# Lipmouse_PCB.net
KiCad netlist of a schematic drawn in EAGLE
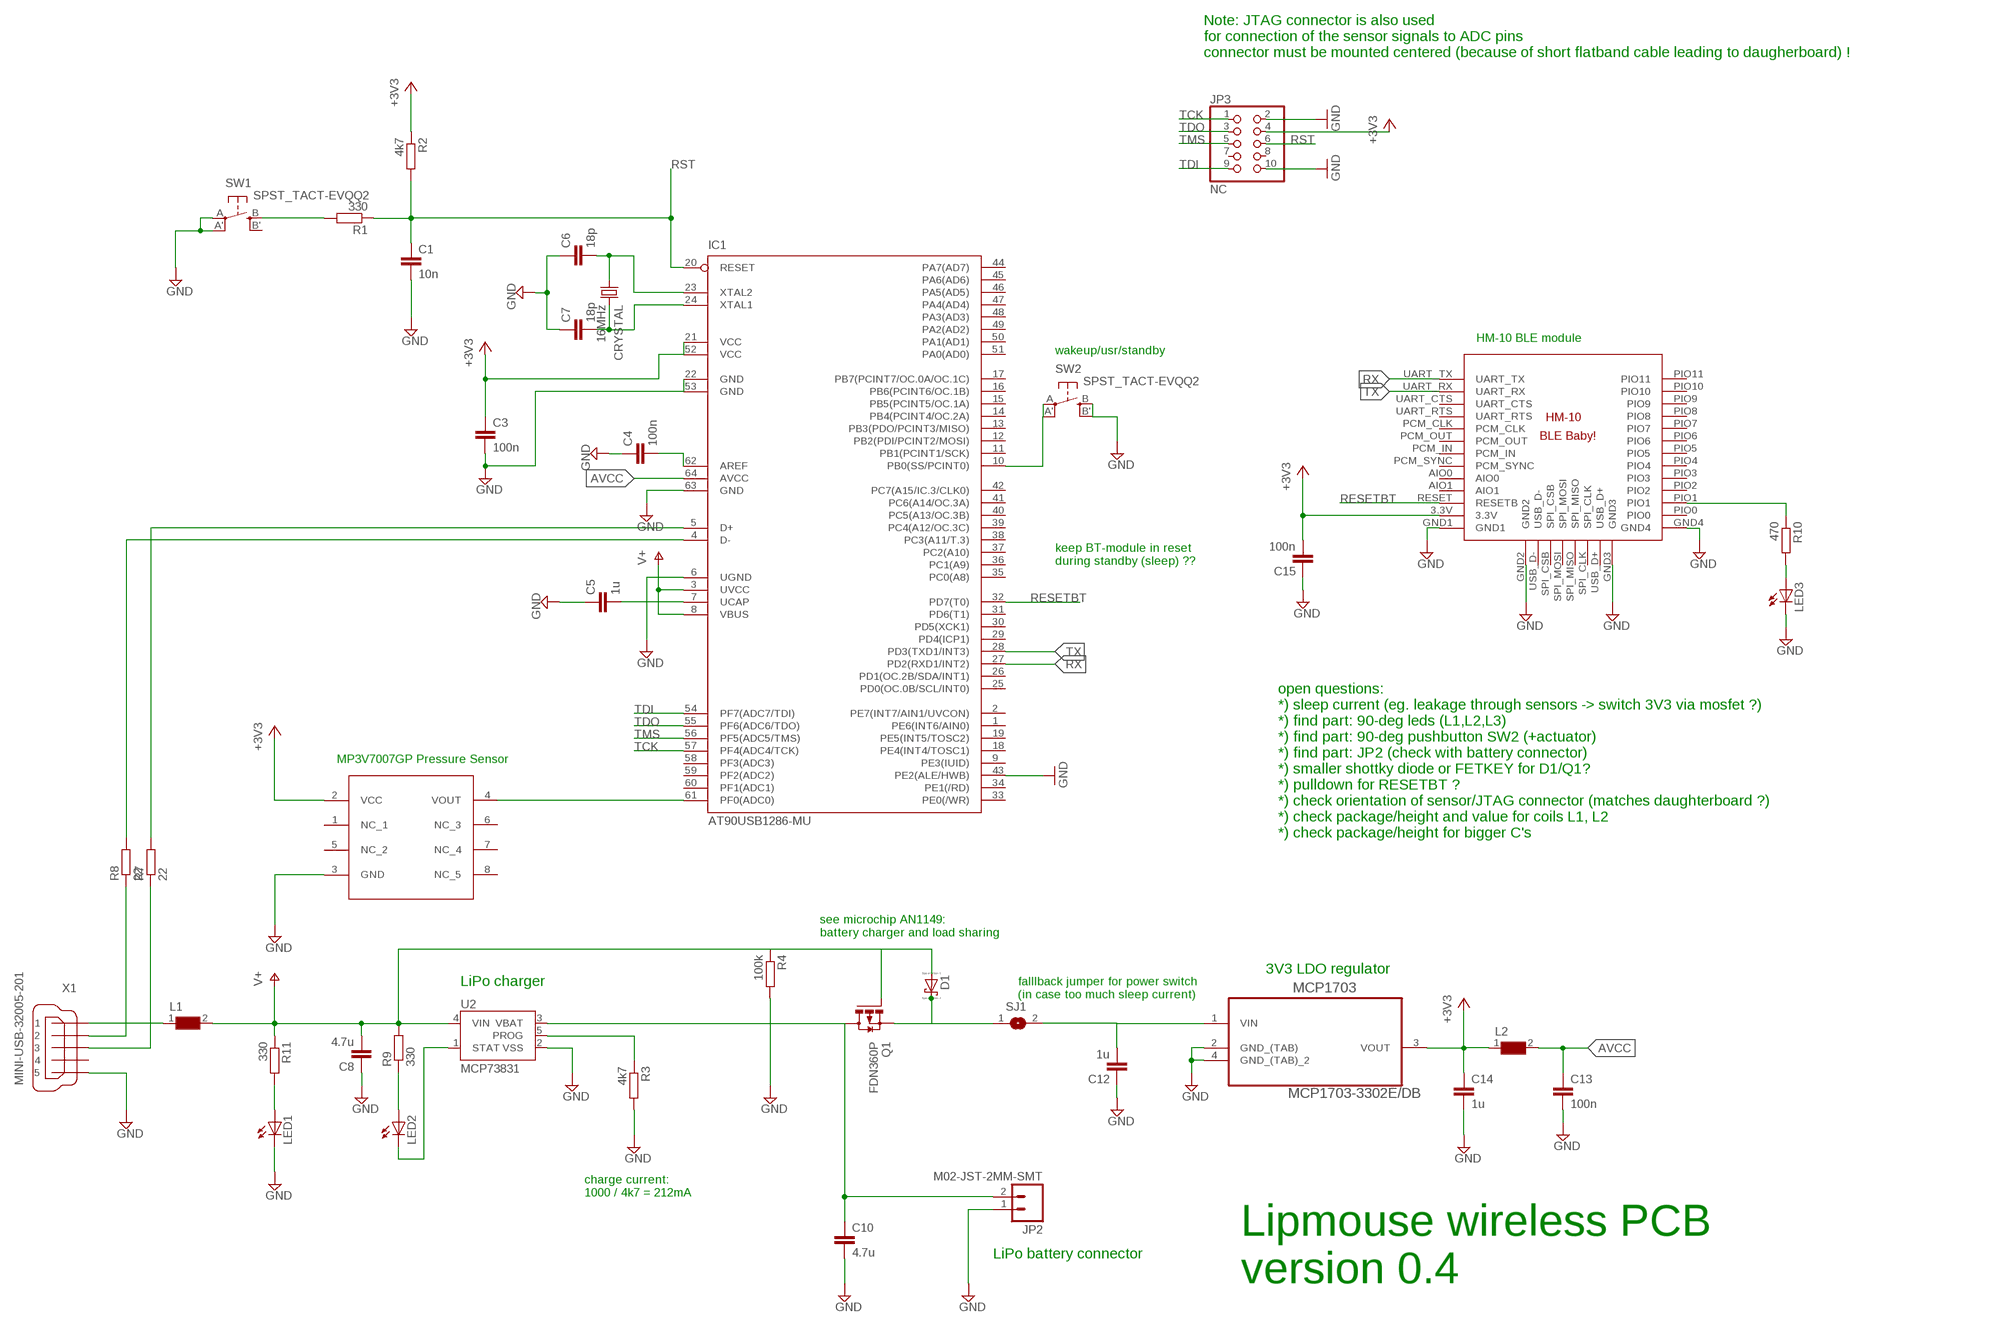
[diagram p0: schematic, sheet 1]

(export (version "E")
  (design (tool "Eeschema 10.0.6"))
  (components
    (comp (ref "C1")
      (value "10n")
      (footprint "eagle-import:C0603")
      (libsource (lib "eagle-import") (part "C-EUC0603"))
    )
    (comp (ref "C3")
      (value "100n")
      (footprint "eagle-import:C0603")
      (libsource (lib "eagle-import") (part "C-EUC0603"))
    )
    (comp (ref "C4")
      (value "100n")
      (footprint "eagle-import:C0603")
      (libsource (lib "eagle-import") (part "C-EUC0603"))
    )
    (comp (ref "C5")
      (value "1u")
      (footprint "eagle-import:C0603")
      (libsource (lib "eagle-import") (part "C-EUC0603"))
    )
    (comp (ref "C6")
      (value "18p")
      (footprint "eagle-import:C0603")
      (libsource (lib "eagle-import") (part "C-EUC0603"))
    )
    (comp (ref "C7")
      (value "18p")
      (footprint "eagle-import:C0603")
      (libsource (lib "eagle-import") (part "C-EUC0603"))
    )
    (comp (ref "C8")
      (value "4.7u")
      (footprint "eagle-import:C0805")
      (libsource (lib "eagle-import") (part "C-EUC0805"))
    )
    (comp (ref "C10")
      (value "4.7u")
      (footprint "eagle-import:C0805")
      (libsource (lib "eagle-import") (part "C-EUC0805"))
    )
    (comp (ref "C12")
      (value "1u")
      (footprint "eagle-import:C0603")
      (libsource (lib "eagle-import") (part "C-EUC0603"))
    )
    (comp (ref "C13")
      (value "100n")
      (footprint "eagle-import:C0603")
      (libsource (lib "eagle-import") (part "C-EUC0603"))
    )
    (comp (ref "C14")
      (value "1u")
      (footprint "eagle-import:C0603")
      (libsource (lib "eagle-import") (part "C-EUC0603"))
    )
    (comp (ref "C15")
      (value "100n")
      (footprint "eagle-import:C0603")
      (libsource (lib "eagle-import") (part "C-EUC0603"))
    )
    (comp (ref "CRYSTAL")
      (value "16MHz")
      (footprint "eagle-import:CRYSTAL-TXC-7A")
      (libsource (lib "eagle-import") (part "CRYSTALTXC-7A"))
    )
    (comp (ref "D1")
      (value "SCHOTTKY-DIODE")
      (footprint "eagle-import:DIODE_SMB")
      (libsource (lib "eagle-import") (part "SCHOTTKY-DIODE"))
    )
    (comp (ref "IC1")
      (value "AT90USB1286-MU")
      (footprint "eagle-import:TQFP64")
      (libsource (lib "eagle-import") (part "AT90USB1287-AU"))
    )
    (comp (ref "JP2")
      (value "M02-JST-2MM-SMT")
      (footprint "eagle-import:JST-2-SMD")
      (libsource (lib "eagle-import") (part "M02-JST-2MM-SMT"))
    )
    (comp (ref "JP3")
      (value "NC")
      (footprint "eagle-import:2X05")
      (libsource (lib "eagle-import") (part "PINHD-2X5"))
    )
    (comp (ref "L1")
      (value "WE-CBF-74279201_0805")
      (footprint "eagle-import:0805")
      (fields (field (name "MPN") "74279201"))
      (libsource (lib "eagle-import") (part "WE-CBF_0805-74279201"))
    )
    (comp (ref "L2")
      (value "WE-CBF-74279201_0805")
      (footprint "eagle-import:0805")
      (fields (field (name "MPN") "74279201"))
      (libsource (lib "eagle-import") (part "WE-CBF_0805-74279201"))
    )
    (comp (ref "LED1")
      (value "LEDSMT1206")
      (footprint "eagle-import:1206")
      (libsource (lib "eagle-import") (part "LEDSMT1206"))
    )
    (comp (ref "LED2")
      (value "LEDSMT1206")
      (footprint "eagle-import:1206")
      (libsource (lib "eagle-import") (part "LEDSMT1206"))
    )
    (comp (ref "LED3")
      (value "LEDSMT1206")
      (footprint "eagle-import:1206")
      (libsource (lib "eagle-import") (part "LEDSMT1206"))
    )
    (comp (ref "MCP1703")
      (value "MCP1703-3302E/DB")
      (footprint "eagle-import:SOT230P700X180-4N")
      (libsource (lib "eagle-import") (part "MCP1703-3302E/DB"))
    )
    (comp (ref "MP3V7007")
      (value "MP3V7007GP")
      (footprint "eagle-import:SMP_MP3V7007")
      (libsource (lib "eagle-import") (part "MP3V7007GP"))
    )
    (comp (ref "Q1")
      (value "FDN360P")
      (footprint "eagle-import:SUPER-SOT3")
      (libsource (lib "eagle-import") (part "FDN360P"))
    )
    (comp (ref "R1")
      (value "330")
      (footprint "eagle-import:R0603")
      (libsource (lib "eagle-import") (part "R-EU_R0603"))
    )
    (comp (ref "R2")
      (value "4k7")
      (footprint "eagle-import:R0603")
      (libsource (lib "eagle-import") (part "R-EU_R0603"))
    )
    (comp (ref "R3")
      (value "4k7")
      (footprint "eagle-import:R0603")
      (libsource (lib "eagle-import") (part "R-EU_R0603"))
    )
    (comp (ref "R4")
      (value "100k")
      (footprint "eagle-import:R0603")
      (libsource (lib "eagle-import") (part "R-EU_R0603"))
    )
    (comp (ref "R7")
      (value "22")
      (footprint "eagle-import:R0603")
      (libsource (lib "eagle-import") (part "R-EU_R0603"))
    )
    (comp (ref "R8")
      (value "22")
      (footprint "eagle-import:R0603")
      (libsource (lib "eagle-import") (part "R-EU_R0603"))
    )
    (comp (ref "R9")
      (value "330")
      (footprint "eagle-import:R0603")
      (libsource (lib "eagle-import") (part "R-EU_R0603"))
    )
    (comp (ref "R10")
      (value "470")
      (footprint "eagle-import:R0603")
      (libsource (lib "eagle-import") (part "R-EU_R0603"))
    )
    (comp (ref "R11")
      (value "330")
      (footprint "eagle-import:R0603")
      (libsource (lib "eagle-import") (part "R-EU_R0603"))
    )
    (comp (ref "SJ1") (value "SJ") (footprint "eagle-import:SJ") (libsource (lib "eagle-import") (part "SJ")))
    (comp (ref "SW1")
      (value "SPST_TACT-EVQQ2")
      (footprint "eagle-import:EVQ-Q2")
      (libsource (lib "eagle-import") (part "SPST_TACT-EVQQ2"))
    )
    (comp (ref "SW2")
      (value "SPST_TACT-EVQQ2")
      (footprint "eagle-import:EVQ-Q2")
      (libsource (lib "eagle-import") (part "SPST_TACT-EVQQ2"))
    )
    (comp (ref "U$1")
      (value "BLE-HM-10")
      (footprint "eagle-import:BLE-HM-10")
      (libsource (lib "eagle-import") (part "BLE-HM-10"))
    )
    (comp (ref "U2")
      (value "MCP73831")
      (footprint "eagle-import:SOT23-5")
      (libsource (lib "eagle-import") (part "MCP73831"))
    )
    (comp (ref "X1")
      (value "MINI-USB-32005-201")
      (footprint "eagle-import:32005-201")
      (libsource (lib "eagle-import") (part "MINI-USB-32005-201"))
    )
  )
  (nets
    (net (code "1") (name "+3V3") (class "Default")
      (node (ref "C14") (pin "1") (pinfunction "1_1") (pintype "passive"))
      (node (ref "C15") (pin "2") (pinfunction "2_2") (pintype "passive"))
      (node (ref "C3") (pin "1") (pinfunction "1_1") (pintype "passive"))
      (node (ref "IC1") (pin "21") (pinfunction "VCC_21") (pintype "power_in"))
      (node (ref "IC1") (pin "52") (pinfunction "VCC_52") (pintype "power_in"))
      (node (ref "JP3") (pin "4") (pinfunction "4_4") (pintype "passive"))
      (node (ref "L2") (pin "1") (pinfunction "1_1") (pintype "passive"))
      (node (ref "MCP1703") (pin "3") (pinfunction "VOUT_3") (pintype "output"))
      (node (ref "MP3V7007") (pin "2") (pinfunction "VCC_2") (pintype "bidirectional"))
      (node (ref "R2") (pin "1") (pinfunction "1_1") (pintype "passive"))
      (node (ref "U$1") (pin "3.3V") (pinfunction "3.3V_3.3V") (pintype "bidirectional"))
    )
    (net (code "2") (name "/RESETBT") (class "Default")
      (node (ref "IC1") (pin "32") (pinfunction "PD7(T0)_32") (pintype "bidirectional"))
      (node (ref "U$1") (pin "RESET") (pinfunction "RESETB_RESET") (pintype "bidirectional"))
    )
    (net (code "3") (name "/RST") (class "Default")
      (node (ref "C1") (pin "1") (pinfunction "1_1") (pintype "passive"))
      (node (ref "IC1") (pin "20") (pinfunction "RESET_20") (pintype "input"))
      (node (ref "JP3") (pin "6") (pinfunction "6_6") (pintype "passive"))
      (node (ref "R1") (pin "1") (pinfunction "1_1") (pintype "passive"))
      (node (ref "R2") (pin "2") (pinfunction "2_2") (pintype "passive"))
    )
    (net (code "4") (name "/TCK") (class "Default")
      (node (ref "IC1") (pin "57") (pinfunction "PF4(ADC4/TCK)_57") (pintype "bidirectional"))
      (node (ref "JP3") (pin "1") (pinfunction "1_1") (pintype "passive"))
    )
    (net (code "5") (name "/TDI") (class "Default")
      (node (ref "IC1") (pin "54") (pinfunction "PF7(ADC7/TDI)_54") (pintype "bidirectional"))
      (node (ref "JP3") (pin "9") (pinfunction "9_9") (pintype "passive"))
    )
    (net (code "6") (name "/TDO") (class "Default")
      (node (ref "IC1") (pin "55") (pinfunction "PF6(ADC6/TDO)_55") (pintype "bidirectional"))
      (node (ref "JP3") (pin "3") (pinfunction "3_3") (pintype "passive"))
    )
    (net (code "7") (name "/TMS") (class "Default")
      (node (ref "IC1") (pin "56") (pinfunction "PF5(ADC5/TMS)_56") (pintype "bidirectional"))
      (node (ref "JP3") (pin "5") (pinfunction "5_5") (pintype "passive"))
    )
    (net (code "8") (name "AVCC") (class "Default")
      (node (ref "C13") (pin "1") (pinfunction "1_1") (pintype "passive"))
      (node (ref "IC1") (pin "64") (pinfunction "AVCC_64") (pintype "bidirectional"))
      (node (ref "L2") (pin "2") (pinfunction "2_2") (pintype "passive"))
    )
    (net (code "9") (name "GND") (class "Default")
      (node (ref "C1") (pin "2") (pinfunction "2_2") (pintype "passive"))
      (node (ref "C10") (pin "2") (pinfunction "2_2") (pintype "passive"))
      (node (ref "C12") (pin "1") (pinfunction "1_1") (pintype "passive"))
      (node (ref "C13") (pin "2") (pinfunction "2_2") (pintype "passive"))
      (node (ref "C14") (pin "2") (pinfunction "2_2") (pintype "passive"))
      (node (ref "C15") (pin "1") (pinfunction "1_1") (pintype "passive"))
      (node (ref "C3") (pin "2") (pinfunction "2_2") (pintype "passive"))
      (node (ref "C4") (pin "1") (pinfunction "1_1") (pintype "passive"))
      (node (ref "C5") (pin "1") (pinfunction "1_1") (pintype "passive"))
      (node (ref "C6") (pin "1") (pinfunction "1_1") (pintype "passive"))
      (node (ref "C7") (pin "1") (pinfunction "1_1") (pintype "passive"))
      (node (ref "C8") (pin "1") (pinfunction "1_1") (pintype "passive"))
      (node (ref "IC1") (pin "22") (pinfunction "GND_22") (pintype "power_in"))
      (node (ref "IC1") (pin "43") (pinfunction "PE2(ALE/HWB)_43") (pintype "bidirectional"))
      (node (ref "IC1") (pin "53") (pinfunction "GND_53") (pintype "power_in"))
      (node (ref "IC1") (pin "6") (pinfunction "UGND_6") (pintype "power_in"))
      (node (ref "IC1") (pin "63") (pinfunction "GND_63") (pintype "power_in"))
      (node (ref "JP2") (pin "1") (pinfunction "2_1") (pintype "passive"))
      (node (ref "JP3") (pin "10") (pinfunction "10_10") (pintype "passive"))
      (node (ref "JP3") (pin "2") (pinfunction "2_2") (pintype "passive"))
      (node (ref "LED1") (pin "C") (pinfunction "C_C") (pintype "passive"))
      (node (ref "LED3") (pin "C") (pinfunction "C_C") (pintype "passive"))
      (node (ref "MCP1703") (pin "2") (pinfunction "GND_(TAB)_2") (pintype "passive"))
      (node (ref "MCP1703") (pin "4") (pinfunction "GND_(TAB)_2_4") (pintype "passive"))
      (node (ref "MP3V7007") (pin "3") (pinfunction "GND_3") (pintype "bidirectional"))
      (node (ref "R3") (pin "2") (pinfunction "2_2") (pintype "passive"))
      (node (ref "R4") (pin "2") (pinfunction "2_2") (pintype "passive"))
      (node (ref "SW1") (pin "A") (pinfunction "P_A") (pintype "passive"))
      (node (ref "SW1") (pin "A'") (pinfunction "P1_A'") (pintype "passive"))
      (node (ref "SW2") (pin "B") (pinfunction "S_B") (pintype "passive"))
      (node (ref "SW2") (pin "B'") (pinfunction "S1_B'") (pintype "passive"))
      (node (ref "U$1") (pin "GND1") (pinfunction "GND1_GND1") (pintype "bidirectional"))
      (node (ref "U$1") (pin "GND2") (pinfunction "GND2_GND2") (pintype "bidirectional"))
      (node (ref "U$1") (pin "GND3") (pinfunction "GND3_GND3") (pintype "bidirectional"))
      (node (ref "U$1") (pin "GND4") (pinfunction "GND4_GND4") (pintype "bidirectional"))
      (node (ref "U2") (pin "2") (pinfunction "VSS_2") (pintype "power_in"))
      (node (ref "X1") (pin "5") (pinfunction "5_5") (pintype "passive"))
    )
    (net (code "10") (name "Net-(CRYSTAL-1)") (class "Default")
      (node (ref "C6") (pin "2") (pinfunction "2_2") (pintype "passive"))
      (node (ref "CRYSTAL") (pin "P$1") (pinfunction "1_P$1") (pintype "passive"))
      (node (ref "IC1") (pin "23") (pinfunction "XTAL2_23") (pintype "bidirectional"))
    )
    (net (code "11") (name "Net-(CRYSTAL-2)") (class "Default")
      (node (ref "C7") (pin "2") (pinfunction "2_2") (pintype "passive"))
      (node (ref "CRYSTAL") (pin "P$2") (pinfunction "2_P$2") (pintype "passive"))
      (node (ref "IC1") (pin "24") (pinfunction "XTAL1_24") (pintype "bidirectional"))
    )
    (net (code "12") (name "Net-(D1-A)") (class "Default")
      (node (ref "D1") (pin "C") (pinfunction "A_C") (pintype "passive"))
      (node (ref "Q1") (pin "2") (pinfunction "S_2") (pintype "passive"))
      (node (ref "SJ1") (pin "1") (pinfunction "1_1") (pintype "passive"))
    )
    (net (code "13") (name "Net-(IC1-AREF)") (class "Default")
      (node (ref "C4") (pin "2") (pinfunction "2_2") (pintype "passive"))
      (node (ref "IC1") (pin "62") (pinfunction "AREF_62") (pintype "bidirectional"))
    )
    (net (code "14") (name "Net-(IC1-D+)") (class "Default")
      (node (ref "IC1") (pin "5") (pinfunction "D+_5") (pintype "bidirectional"))
      (node (ref "R7") (pin "2") (pinfunction "2_2") (pintype "passive"))
    )
    (net (code "15") (name "Net-(IC1-D-)") (class "Default")
      (node (ref "IC1") (pin "4") (pinfunction "D-_4") (pintype "bidirectional"))
      (node (ref "R8") (pin "2") (pinfunction "2_2") (pintype "passive"))
    )
    (net (code "16") (name "Net-(IC1-PB0(SS{slash}PCINT0))") (class "Default")
      (node (ref "IC1") (pin "10") (pinfunction "PB0(SS/PCINT0)_10") (pintype "bidirectional"))
      (node (ref "SW2") (pin "A") (pinfunction "P_A") (pintype "passive"))
      (node (ref "SW2") (pin "A'") (pinfunction "P1_A'") (pintype "passive"))
    )
    (net (code "17") (name "Net-(IC1-PF0(ADC0))") (class "Default")
      (node (ref "IC1") (pin "61") (pinfunction "PF0(ADC0)_61") (pintype "bidirectional"))
      (node (ref "MP3V7007") (pin "4") (pinfunction "VOUT_4") (pintype "bidirectional"))
    )
    (net (code "18") (name "Net-(IC1-UCAP)") (class "Default")
      (node (ref "C5") (pin "2") (pinfunction "2_2") (pintype "passive"))
      (node (ref "IC1") (pin "7") (pinfunction "UCAP_7") (pintype "power_in"))
    )
    (net (code "19") (name "Net-(JP2-1)") (class "Default")
      (node (ref "C10") (pin "1") (pinfunction "1_1") (pintype "passive"))
      (node (ref "JP2") (pin "2") (pinfunction "1_2") (pintype "passive"))
      (node (ref "Q1") (pin "3") (pinfunction "D_3") (pintype "passive"))
      (node (ref "U2") (pin "3") (pinfunction "VBAT_3") (pintype "power_in"))
    )
    (net (code "20") (name "Net-(L1-Pad1)") (class "Default")
      (node (ref "L1") (pin "1") (pinfunction "1_1") (pintype "passive"))
      (node (ref "X1") (pin "1") (pinfunction "1_1") (pintype "passive"))
    )
    (net (code "21") (name "Net-(LED1-PadA)") (class "Default")
      (node (ref "LED1") (pin "A") (pinfunction "A_A") (pintype "passive"))
      (node (ref "R11") (pin "2") (pinfunction "2_2") (pintype "passive"))
    )
    (net (code "22") (name "Net-(LED2-PadA)") (class "Default")
      (node (ref "LED2") (pin "A") (pinfunction "A_A") (pintype "passive"))
      (node (ref "R9") (pin "1") (pinfunction "1_1") (pintype "passive"))
    )
    (net (code "23") (name "Net-(LED3-PadA)") (class "Default")
      (node (ref "LED3") (pin "A") (pinfunction "A_A") (pintype "passive"))
      (node (ref "R10") (pin "2") (pinfunction "2_2") (pintype "passive"))
    )
    (net (code "24") (name "Net-(MCP1703-VIN)") (class "Default")
      (node (ref "C12") (pin "2") (pinfunction "2_2") (pintype "passive"))
      (node (ref "MCP1703") (pin "1") (pinfunction "VIN_1") (pintype "input"))
      (node (ref "SJ1") (pin "2") (pinfunction "2_2") (pintype "passive"))
    )
    (net (code "25") (name "Net-(R7-Pad1)") (class "Default")
      (node (ref "R7") (pin "1") (pinfunction "1_1") (pintype "passive"))
      (node (ref "X1") (pin "3") (pinfunction "3_3") (pintype "passive"))
    )
    (net (code "26") (name "Net-(R8-Pad1)") (class "Default")
      (node (ref "R8") (pin "1") (pinfunction "1_1") (pintype "passive"))
      (node (ref "X1") (pin "2") (pinfunction "2_2") (pintype "passive"))
    )
    (net (code "27") (name "Net-(R10-Pad1)") (class "Default")
      (node (ref "R10") (pin "1") (pinfunction "1_1") (pintype "passive"))
      (node (ref "U$1") (pin "PIO1") (pinfunction "PIO1_PIO1") (pintype "bidirectional"))
    )
    (net (code "28") (name "Net-(SW1-S)") (class "Default")
      (node (ref "R1") (pin "2") (pinfunction "2_2") (pintype "passive"))
      (node (ref "SW1") (pin "B") (pinfunction "S_B") (pintype "passive"))
    )
    (net (code "29") (name "Net-(U2-PROG)") (class "Default")
      (node (ref "R3") (pin "1") (pinfunction "1_1") (pintype "passive"))
      (node (ref "U2") (pin "5") (pinfunction "PROG_5") (pintype "input"))
    )
    (net (code "30") (name "Net-(U2-STAT)") (class "Default")
      (node (ref "LED2") (pin "C") (pinfunction "C_C") (pintype "passive"))
      (node (ref "U2") (pin "1") (pinfunction "STAT_1") (pintype "output"))
    )
    (net (code "31") (name "RX") (class "Default")
      (node (ref "IC1") (pin "27") (pinfunction "PD2(RXD1/INT2)_27") (pintype "bidirectional"))
      (node (ref "U$1") (pin "UART_TX") (pinfunction "UART_TX_UART_TX") (pintype "bidirectional"))
    )
    (net (code "32") (name "TX") (class "Default")
      (node (ref "IC1") (pin "28") (pinfunction "PD3(TXD1/INT3)_28") (pintype "bidirectional"))
      (node (ref "U$1") (pin "UART_RX") (pinfunction "UART_RX_UART_RX") (pintype "bidirectional"))
    )
    (net (code "33") (name "V+") (class "Default")
      (node (ref "C8") (pin "2") (pinfunction "2_2") (pintype "passive"))
      (node (ref "D1") (pin "A") (pinfunction "C_A") (pintype "passive"))
      (node (ref "IC1") (pin "3") (pinfunction "UVCC_3") (pintype "power_in"))
      (node (ref "IC1") (pin "8") (pinfunction "VBUS_8") (pintype "power_in"))
      (node (ref "L1") (pin "2") (pinfunction "2_2") (pintype "passive"))
      (node (ref "Q1") (pin "1") (pinfunction "G_1") (pintype "passive"))
      (node (ref "R11") (pin "1") (pinfunction "1_1") (pintype "passive"))
      (node (ref "R4") (pin "1") (pinfunction "1_1") (pintype "passive"))
      (node (ref "R9") (pin "2") (pinfunction "2_2") (pintype "passive"))
      (node (ref "U2") (pin "4") (pinfunction "VIN_4") (pintype "power_in"))
    )
    (net (code "34") (name "unconnected-(IC1-PA0(AD0)-Pad51)") (class "Default")
      (node (ref "IC1") (pin "51") (pinfunction "PA0(AD0)_51") (pintype "bidirectional"))
    )
    (net (code "35") (name "unconnected-(IC1-PA1(AD1)-Pad50)") (class "Default")
      (node (ref "IC1") (pin "50") (pinfunction "PA1(AD1)_50") (pintype "bidirectional"))
    )
    (net (code "36") (name "unconnected-(IC1-PA2(AD2)-Pad49)") (class "Default")
      (node (ref "IC1") (pin "49") (pinfunction "PA2(AD2)_49") (pintype "bidirectional"))
    )
    (net (code "37") (name "unconnected-(IC1-PA3(AD3)-Pad48)") (class "Default")
      (node (ref "IC1") (pin "48") (pinfunction "PA3(AD3)_48") (pintype "bidirectional"))
    )
    (net (code "38") (name "unconnected-(IC1-PA4(AD4)-Pad47)") (class "Default")
      (node (ref "IC1") (pin "47") (pinfunction "PA4(AD4)_47") (pintype "bidirectional"))
    )
    (net (code "39") (name "unconnected-(IC1-PA5(AD5)-Pad46)") (class "Default")
      (node (ref "IC1") (pin "46") (pinfunction "PA5(AD5)_46") (pintype "bidirectional"))
    )
    (net (code "40") (name "unconnected-(IC1-PA6(AD6)-Pad45)") (class "Default")
      (node (ref "IC1") (pin "45") (pinfunction "PA6(AD6)_45") (pintype "bidirectional"))
    )
    (net (code "41") (name "unconnected-(IC1-PA7(AD7)-Pad44)") (class "Default")
      (node (ref "IC1") (pin "44") (pinfunction "PA7(AD7)_44") (pintype "bidirectional"))
    )
    (net (code "42") (name "unconnected-(IC1-PB1(PCINT1{slash}SCK)-Pad11)") (class "Default")
      (node (ref "IC1") (pin "11") (pinfunction "PB1(PCINT1/SCK)_11") (pintype "bidirectional"))
    )
    (net (code "43") (name "unconnected-(IC1-PB2(PDI{slash}PCINT2{slash}MOSI)-Pad12)") (class "Default")
      (node (ref "IC1") (pin "12") (pinfunction "PB2(PDI/PCINT2/MOSI)_12") (pintype "bidirectional"))
    )
    (net (code "44") (name "unconnected-(IC1-PB3(PDO{slash}PCINT3{slash}MISO)-Pad13)") (class "Default")
      (node (ref "IC1") (pin "13") (pinfunction "PB3(PDO/PCINT3/MISO)_13") (pintype "bidirectional"))
    )
    (net (code "45") (name "unconnected-(IC1-PB4(PCINT4{slash}OC.2A)-Pad14)") (class "Default")
      (node (ref "IC1") (pin "14") (pinfunction "PB4(PCINT4/OC.2A)_14") (pintype "bidirectional"))
    )
    (net (code "46") (name "unconnected-(IC1-PB5(PCINT5{slash}OC.1A)-Pad15)") (class "Default")
      (node (ref "IC1") (pin "15") (pinfunction "PB5(PCINT5/OC.1A)_15") (pintype "bidirectional"))
    )
    (net (code "47") (name "unconnected-(IC1-PB6(PCINT6{slash}OC.1B)-Pad16)") (class "Default")
      (node (ref "IC1") (pin "16") (pinfunction "PB6(PCINT6/OC.1B)_16") (pintype "bidirectional"))
    )
    (net (code "48") (name "unconnected-(IC1-PB7(PCINT7{slash}OC.0A{slash}OC.1C)-Pad17)") (class "Default")
      (node (ref "IC1") (pin "17") (pinfunction "PB7(PCINT7/OC.0A/OC.1C)_17") (pintype "bidirectional"))
    )
    (net (code "49") (name "unconnected-(IC1-PC0(A8)-Pad35)") (class "Default")
      (node (ref "IC1") (pin "35") (pinfunction "PC0(A8)_35") (pintype "bidirectional"))
    )
    (net (code "50") (name "unconnected-(IC1-PC1(A9)-Pad36)") (class "Default")
      (node (ref "IC1") (pin "36") (pinfunction "PC1(A9)_36") (pintype "bidirectional"))
    )
    (net (code "51") (name "unconnected-(IC1-PC2(A10)-Pad37)") (class "Default")
      (node (ref "IC1") (pin "37") (pinfunction "PC2(A10)_37") (pintype "bidirectional"))
    )
    (net (code "52") (name "unconnected-(IC1-PC3(A11{slash}T.3)-Pad38)") (class "Default")
      (node (ref "IC1") (pin "38") (pinfunction "PC3(A11/T.3)_38") (pintype "bidirectional"))
    )
    (net (code "53") (name "unconnected-(IC1-PC4(A12{slash}OC.3C)-Pad39)") (class "Default")
      (node (ref "IC1") (pin "39") (pinfunction "PC4(A12/OC.3C)_39") (pintype "bidirectional"))
    )
    (net (code "54") (name "unconnected-(IC1-PC5(A13{slash}OC.3B)-Pad40)") (class "Default")
      (node (ref "IC1") (pin "40") (pinfunction "PC5(A13/OC.3B)_40") (pintype "bidirectional"))
    )
    (net (code "55") (name "unconnected-(IC1-PC6(A14{slash}OC.3A)-Pad41)") (class "Default")
      (node (ref "IC1") (pin "41") (pinfunction "PC6(A14/OC.3A)_41") (pintype "bidirectional"))
    )
    (net (code "56") (name "unconnected-(IC1-PC7(A15{slash}IC.3{slash}CLK0)-Pad42)") (class "Default")
      (node (ref "IC1") (pin "42") (pinfunction "PC7(A15/IC.3/CLK0)_42") (pintype "bidirectional"))
    )
    (net (code "57") (name "unconnected-(IC1-PD0(OC.0B{slash}SCL{slash}INT0)-Pad25)") (class "Default")
      (node (ref "IC1") (pin "25") (pinfunction "PD0(OC.0B/SCL/INT0)_25") (pintype "bidirectional"))
    )
    (net (code "58") (name "unconnected-(IC1-PD1(OC.2B{slash}SDA{slash}INT1)-Pad26)") (class "Default")
      (node (ref "IC1") (pin "26") (pinfunction "PD1(OC.2B/SDA/INT1)_26") (pintype "bidirectional"))
    )
    (net (code "59") (name "unconnected-(IC1-PD4(ICP1)-Pad29)") (class "Default")
      (node (ref "IC1") (pin "29") (pinfunction "PD4(ICP1)_29") (pintype "bidirectional"))
    )
    (net (code "60") (name "unconnected-(IC1-PD5(XCK1)-Pad30)") (class "Default")
      (node (ref "IC1") (pin "30") (pinfunction "PD5(XCK1)_30") (pintype "bidirectional"))
    )
    (net (code "61") (name "unconnected-(IC1-PD6(T1)-Pad31)") (class "Default")
      (node (ref "IC1") (pin "31") (pinfunction "PD6(T1)_31") (pintype "bidirectional"))
    )
    (net (code "62") (name "unconnected-(IC1-PE0({slash}WR)-Pad33)") (class "Default")
      (node (ref "IC1") (pin "33") (pinfunction "PE0(/WR)_33") (pintype "bidirectional"))
    )
    (net (code "63") (name "unconnected-(IC1-PE1({slash}RD)-Pad34)") (class "Default")
      (node (ref "IC1") (pin "34") (pinfunction "PE1(/RD)_34") (pintype "bidirectional"))
    )
    (net (code "64") (name "unconnected-(IC1-PE3(IUID)-Pad9)") (class "Default")
      (node (ref "IC1") (pin "9") (pinfunction "PE3(IUID)_9") (pintype "bidirectional"))
    )
    (net (code "65") (name "unconnected-(IC1-PE4(INT4{slash}TOSC1)-Pad18)") (class "Default")
      (node (ref "IC1") (pin "18") (pinfunction "PE4(INT4/TOSC1)_18") (pintype "bidirectional"))
    )
    (net (code "66") (name "unconnected-(IC1-PE5(INT5{slash}TOSC2)-Pad19)") (class "Default")
      (node (ref "IC1") (pin "19") (pinfunction "PE5(INT5/TOSC2)_19") (pintype "bidirectional"))
    )
    (net (code "67") (name "unconnected-(IC1-PE6(INT6{slash}AIN0)-Pad1)") (class "Default")
      (node (ref "IC1") (pin "1") (pinfunction "PE6(INT6/AIN0)_1") (pintype "bidirectional"))
    )
    (net (code "68") (name "unconnected-(IC1-PE7(INT7{slash}AIN1{slash}UVCON)-Pad2)") (class "Default")
      (node (ref "IC1") (pin "2") (pinfunction "PE7(INT7/AIN1/UVCON)_2") (pintype "bidirectional"))
    )
    (net (code "69") (name "unconnected-(IC1-PF1(ADC1)-Pad60)") (class "Default")
      (node (ref "IC1") (pin "60") (pinfunction "PF1(ADC1)_60") (pintype "bidirectional"))
    )
    (net (code "70") (name "unconnected-(IC1-PF2(ADC2)-Pad59)") (class "Default")
      (node (ref "IC1") (pin "59") (pinfunction "PF2(ADC2)_59") (pintype "bidirectional"))
    )
    (net (code "71") (name "unconnected-(IC1-PF3(ADC3)-Pad58)") (class "Default")
      (node (ref "IC1") (pin "58") (pinfunction "PF3(ADC3)_58") (pintype "bidirectional"))
    )
    (net (code "72") (name "unconnected-(JP3-Pad7)") (class "Default")
      (node (ref "JP3") (pin "7") (pinfunction "7_7") (pintype "passive"))
    )
    (net (code "73") (name "unconnected-(JP3-Pad8)") (class "Default")
      (node (ref "JP3") (pin "8") (pinfunction "8_8") (pintype "passive"))
    )
    (net (code "74") (name "unconnected-(MP3V7007-NC_1-Pad1)") (class "Default")
      (node (ref "MP3V7007") (pin "1") (pinfunction "NC_1_1") (pintype "bidirectional"))
    )
    (net (code "75") (name "unconnected-(MP3V7007-NC_2-Pad5)") (class "Default")
      (node (ref "MP3V7007") (pin "5") (pinfunction "NC_2_5") (pintype "bidirectional"))
    )
    (net (code "76") (name "unconnected-(MP3V7007-NC_3-Pad6)") (class "Default")
      (node (ref "MP3V7007") (pin "6") (pinfunction "NC_3_6") (pintype "bidirectional"))
    )
    (net (code "77") (name "unconnected-(MP3V7007-NC_4-Pad7)") (class "Default")
      (node (ref "MP3V7007") (pin "7") (pinfunction "NC_4_7") (pintype "bidirectional"))
    )
    (net (code "78") (name "unconnected-(MP3V7007-NC_5-Pad8)") (class "Default")
      (node (ref "MP3V7007") (pin "8") (pinfunction "NC_5_8") (pintype "bidirectional"))
    )
    (net (code "79") (name "unconnected-(SW1-S1-PadB')") (class "Default")
      (node (ref "SW1") (pin "B'") (pinfunction "S1_B'") (pintype "passive"))
    )
    (net (code "80") (name "unconnected-(U$1-PadAIO0)") (class "Default")
      (node (ref "U$1") (pin "AIO0") (pinfunction "AIO0_AIO0") (pintype "bidirectional"))
    )
    (net (code "81") (name "unconnected-(U$1-PadAIO1)") (class "Default")
      (node (ref "U$1") (pin "AIO1") (pinfunction "AIO1_AIO1") (pintype "bidirectional"))
    )
    (net (code "82") (name "unconnected-(U$1-PadPCM_CLK)") (class "Default")
      (node (ref "U$1") (pin "PCM_CLK") (pinfunction "PCM_CLK_PCM_CLK") (pintype "bidirectional"))
    )
    (net (code "83") (name "unconnected-(U$1-PadPCM_IN)") (class "Default")
      (node (ref "U$1") (pin "PCM_IN") (pinfunction "PCM_IN_PCM_IN") (pintype "bidirectional"))
    )
    (net (code "84") (name "unconnected-(U$1-PadPCM_OUT)") (class "Default")
      (node (ref "U$1") (pin "PCM_OUT") (pinfunction "PCM_OUT_PCM_OUT") (pintype "bidirectional"))
    )
    (net (code "85") (name "unconnected-(U$1-PadPCM_SYNC)") (class "Default")
      (node (ref "U$1") (pin "PCM_SYNC") (pinfunction "PCM_SYNC_PCM_SYNC") (pintype "bidirectional"))
    )
    (net (code "86") (name "unconnected-(U$1-PadPIO0)") (class "Default")
      (node (ref "U$1") (pin "PIO0") (pinfunction "PIO0_PIO0") (pintype "bidirectional"))
    )
    (net (code "87") (name "unconnected-(U$1-PadPIO2)") (class "Default")
      (node (ref "U$1") (pin "PIO2") (pinfunction "PIO2_PIO2") (pintype "bidirectional"))
    )
    (net (code "88") (name "unconnected-(U$1-PadPIO3)") (class "Default")
      (node (ref "U$1") (pin "PIO3") (pinfunction "PIO3_PIO3") (pintype "bidirectional"))
    )
    (net (code "89") (name "unconnected-(U$1-PadPIO4)") (class "Default")
      (node (ref "U$1") (pin "PIO4") (pinfunction "PIO4_PIO4") (pintype "bidirectional"))
    )
    (net (code "90") (name "unconnected-(U$1-PadPIO5)") (class "Default")
      (node (ref "U$1") (pin "PIO5") (pinfunction "PIO5_PIO5") (pintype "bidirectional"))
    )
    (net (code "91") (name "unconnected-(U$1-PadPIO6)") (class "Default")
      (node (ref "U$1") (pin "PIO6") (pinfunction "PIO6_PIO6") (pintype "bidirectional"))
    )
    (net (code "92") (name "unconnected-(U$1-PadPIO7)") (class "Default")
      (node (ref "U$1") (pin "PIO7") (pinfunction "PIO7_PIO7") (pintype "bidirectional"))
    )
    (net (code "93") (name "unconnected-(U$1-PadPIO8)") (class "Default")
      (node (ref "U$1") (pin "PIO8") (pinfunction "PIO8_PIO8") (pintype "bidirectional"))
    )
    (net (code "94") (name "unconnected-(U$1-PadPIO9)") (class "Default")
      (node (ref "U$1") (pin "PIO9") (pinfunction "PIO9_PIO9") (pintype "bidirectional"))
    )
    (net (code "95") (name "unconnected-(U$1-PadPIO10)") (class "Default")
      (node (ref "U$1") (pin "PIO10") (pinfunction "PIO10_PIO10") (pintype "bidirectional"))
    )
    (net (code "96") (name "unconnected-(U$1-PadPIO11)") (class "Default")
      (node (ref "U$1") (pin "PIO11") (pinfunction "PIO11_PIO11") (pintype "bidirectional"))
    )
    (net (code "97") (name "unconnected-(U$1-PadSPI_CLK)") (class "Default")
      (node (ref "U$1") (pin "SPI_CLK") (pinfunction "SPI_CLK_SPI_CLK") (pintype "bidirectional"))
    )
    (net (code "98") (name "unconnected-(U$1-PadSPI_CSB)") (class "Default")
      (node (ref "U$1") (pin "SPI_CSB") (pinfunction "SPI_CSB_SPI_CSB") (pintype "bidirectional"))
    )
    (net (code "99") (name "unconnected-(U$1-PadSPI_MISO)") (class "Default")
      (node (ref "U$1") (pin "SPI_MISO") (pinfunction "SPI_MISO_SPI_MISO") (pintype "bidirectional"))
    )
    (net (code "100") (name "unconnected-(U$1-PadSPI_MOSI)") (class "Default")
      (node (ref "U$1") (pin "SPI_MOSI") (pinfunction "SPI_MOSI_SPI_MOSI") (pintype "bidirectional"))
    )
    (net (code "101") (name "unconnected-(U$1-PadUART_CTS)") (class "Default")
      (node (ref "U$1") (pin "UART_CTS") (pinfunction "UART_CTS_UART_CTS") (pintype "bidirectional"))
    )
    (net (code "102") (name "unconnected-(U$1-PadUART_RTS)") (class "Default")
      (node (ref "U$1") (pin "UART_RTS") (pinfunction "UART_RTS_UART_RTS") (pintype "bidirectional"))
    )
    (net (code "103") (name "unconnected-(U$1-PadUSB_D+)") (class "Default")
      (node (ref "U$1") (pin "USB_D+") (pinfunction "USB_D+_USB_D+") (pintype "bidirectional"))
    )
    (net (code "104") (name "unconnected-(U$1-PadUSB_D-)") (class "Default")
      (node (ref "U$1") (pin "USB_D-") (pinfunction "USB_D-_USB_D-") (pintype "bidirectional"))
    )
    (net (code "105") (name "unconnected-(X1-Pad4)") (class "Default")
      (node (ref "X1") (pin "4") (pinfunction "4_4") (pintype "passive"))
    )
  )
)
